# LCmeter0-LCD-mounted-PIC-COMP.net
KiCad netlist of a schematic drawn in EAGLE
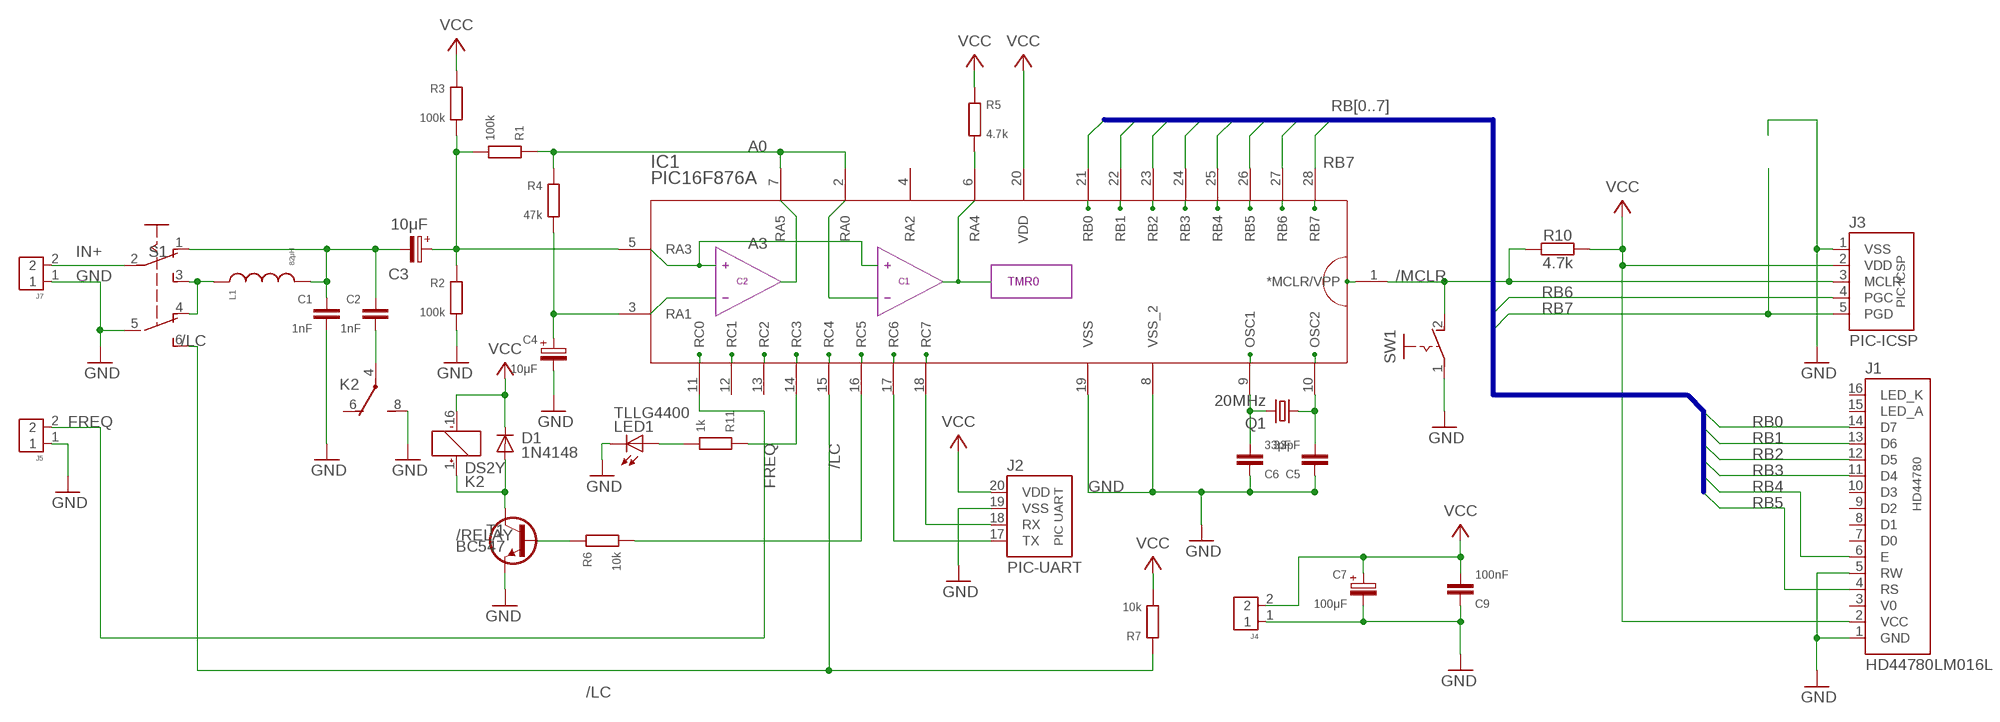
[diagram p0: schematic, sheet 1]

(export (version "E")
  (design (tool "Eeschema 10.0.6"))
  (components
    (comp (ref "C1")
      (value "1nF")
      (footprint "eagle-import:C050-025X060")
      (libsource (lib "eagle-import") (part "C025-025X060"))
    )
    (comp (ref "C2")
      (value "1nF")
      (footprint "eagle-import:C050-025X060")
      (libsource (lib "eagle-import") (part "C025-025X060"))
    )
    (comp (ref "C3")
      (value "10μF")
      (footprint "eagle-import:E2,5-4")
      (libsource (lib "eagle-import") (part "CPOLE2,5-4"))
    )
    (comp (ref "C4")
      (value "10μF")
      (footprint "eagle-import:E2,5-4")
      (libsource (lib "eagle-import") (part "CPOLE2,5-4"))
    )
    (comp (ref "C5")
      (value "33pF")
      (footprint "eagle-import:C025-020X036")
      (libsource (lib "eagle-import") (part "C025-020X036"))
    )
    (comp (ref "C6")
      (value "33pF")
      (footprint "eagle-import:C025-020X036")
      (libsource (lib "eagle-import") (part "C025-020X036"))
    )
    (comp (ref "C7")
      (value "100μF")
      (footprint "eagle-import:E2,5-5")
      (libsource (lib "eagle-import") (part "CPOLE2.5-5"))
    )
    (comp (ref "C9")
      (value "100nF")
      (footprint "eagle-import:C025-020X036_V")
      (libsource (lib "eagle-import") (part "C025-020X036/V"))
    )
    (comp (ref "D1")
      (value "1N4148")
      (footprint "eagle-import:DO34-7")
      (libsource (lib "eagle-import") (part "1N414834-7"))
    )
    (comp (ref "IC1")
      (value "PIC16F876A")
      (footprint "eagle-import:DIL28-3")
      (libsource (lib "eagle-import") (part "PIC16F876A-X/SP-COMP-B-A"))
    )
    (comp (ref "J1")
      (value "HD44780LM016L")
      (footprint "eagle-import:LM016L-HD44780")
      (libsource (lib "eagle-import") (part "HD44780LM016L"))
    )
    (comp (ref "J2")
      (value "PIC-UART")
      (footprint "eagle-import:PIC-UART")
      (libsource (lib "eagle-import") (part "PIC-UART"))
    )
    (comp (ref "J3")
      (value "PIC-ICSP")
      (footprint "eagle-import:PIC-ICSP")
      (libsource (lib "eagle-import") (part "PIC-ICSPICSP"))
    )
    (comp (ref "J4")
      (value "J4")
      (footprint "eagle-import:CONN-2P")
      (libsource (lib "eagle-import") (part "CONN-2P2P/H"))
    )
    (comp (ref "J5")
      (value "CONN-2P2P/V")
      (footprint "eagle-import:CONN-2P-V")
      (libsource (lib "eagle-import") (part "CONN-2P2P/V"))
    )
    (comp (ref "J7")
      (value "CONN-2P2P/V")
      (footprint "eagle-import:CONN-2P-V")
      (libsource (lib "eagle-import") (part "CONN-2P2P/V"))
    )
    (comp (ref "K2")
      (value "DS2Y")
      (footprint "eagle-import:DS2Y")
      (fields (field (name "MPN") "DS2Y-S-DC5V"))
      (libsource (lib "eagle-import") (part "DS2Y-S-DC5V"))
    )
    (comp (ref "L1")
      (value "82μH")
      (footprint "eagle-import:0207_10")
      (libsource (lib "eagle-import") (part "LAXIAL"))
    )
    (comp (ref "LED1")
      (value "TLLG4400")
      (footprint "eagle-import:LED3MM")
      (fields (field (name "MF") "VISHAY SEMICONDUCTOR"))
      (libsource (lib "eagle-import") (part "TLLG4400"))
    )
    (comp (ref "Q1")
      (value "20MHz")
      (footprint "eagle-import:HC49")
      (libsource (lib "eagle-import") (part "CRYSTALHC49"))
    )
    (comp (ref "R1")
      (value "100k")
      (footprint "eagle-import:0202_7")
      (libsource (lib "eagle-import") (part "R0202/7"))
    )
    (comp (ref "R2")
      (value "100k")
      (footprint "eagle-import:0202_7")
      (libsource (lib "eagle-import") (part "R0202/7"))
    )
    (comp (ref "R3")
      (value "100k")
      (footprint "eagle-import:0202_7")
      (libsource (lib "eagle-import") (part "R0202/7"))
    )
    (comp (ref "R4")
      (value "47k")
      (footprint "eagle-import:0202_7")
      (libsource (lib "eagle-import") (part "R0202/7"))
    )
    (comp (ref "R5")
      (value "4.7k")
      (footprint "eagle-import:0202_7")
      (libsource (lib "eagle-import") (part "R0202/7"))
    )
    (comp (ref "R6")
      (value "10k")
      (footprint "eagle-import:0202_10")
      (libsource (lib "eagle-import") (part "R0202/10"))
    )
    (comp (ref "R7")
      (value "10k")
      (footprint "eagle-import:0202_7")
      (libsource (lib "eagle-import") (part "R0202/7"))
    )
    (comp (ref "R10")
      (value "4.7k")
      (footprint "eagle-import:0202_7")
      (libsource (lib "eagle-import") (part "R0202/7"))
    )
    (comp (ref "R11")
      (value "1k")
      (footprint "eagle-import:0202_10-V")
      (libsource (lib "eagle-import") (part "R0202/10-V"))
    )
    (comp (ref "S1")
      (value "SL-SW-2P-2T")
      (footprint "eagle-import:SLSW-2P2T")
      (libsource (lib "eagle-import") (part "SL-SW-2P-2T"))
    )
    (comp (ref "SW1")
      (value "PB-1P-1T")
      (footprint "eagle-import:PB-1P1T")
      (libsource (lib "eagle-import") (part "PB-1P-1T"))
    )
    (comp (ref "T1")
      (value "BC547")
      (footprint "eagle-import:TO92-CBE")
      (libsource (lib "eagle-import") (part "BC547CBE"))
    )
  )
  (nets
    (net (code "1") (name "/A0") (class "Default")
      (node (ref "IC1") (pin "2") (pinfunction "RA0_2") (pintype "passive"))
      (node (ref "IC1") (pin "7") (pinfunction "RA5_7") (pintype "passive"))
      (node (ref "R1") (pin "2") (pinfunction "2_2") (pintype "passive"))
      (node (ref "R4") (pin "2") (pinfunction "2_2") (pintype "passive"))
    )
    (net (code "2") (name "/A3") (class "Default")
      (node (ref "C3") (pin "+") (pinfunction "+_+") (pintype "passive"))
      (node (ref "IC1") (pin "5") (pinfunction "RA3_5") (pintype "passive"))
      (node (ref "R1") (pin "1") (pinfunction "1_1") (pintype "passive"))
      (node (ref "R2") (pin "2") (pinfunction "2_2") (pintype "passive"))
      (node (ref "R3") (pin "1") (pinfunction "1_1") (pintype "passive"))
    )
    (net (code "3") (name "/FREQ") (class "Default")
      (node (ref "IC1") (pin "11") (pinfunction "RC0_11") (pintype "passive"))
      (node (ref "J5") (pin "2") (pinfunction "2_2") (pintype "bidirectional"))
    )
    (net (code "4") (name "/IN+") (class "Default")
      (node (ref "J7") (pin "2") (pinfunction "2_2") (pintype "bidirectional"))
      (node (ref "S1") (pin "2") (pinfunction "P_2") (pintype "passive"))
    )
    (net (code "5") (name "/RB0") (class "Default")
      (node (ref "IC1") (pin "21") (pinfunction "RB0_21") (pintype "passive"))
      (node (ref "J1") (pin "14") (pinfunction "D7_14") (pintype "passive"))
    )
    (net (code "6") (name "/RB1") (class "Default")
      (node (ref "IC1") (pin "22") (pinfunction "RB1_22") (pintype "passive"))
      (node (ref "J1") (pin "13") (pinfunction "D6_13") (pintype "passive"))
    )
    (net (code "7") (name "/RB2") (class "Default")
      (node (ref "IC1") (pin "23") (pinfunction "RB2_23") (pintype "passive"))
      (node (ref "J1") (pin "12") (pinfunction "D5_12") (pintype "passive"))
    )
    (net (code "8") (name "/RB3") (class "Default")
      (node (ref "IC1") (pin "24") (pinfunction "RB3_24") (pintype "passive"))
      (node (ref "J1") (pin "11") (pinfunction "D4_11") (pintype "passive"))
    )
    (net (code "9") (name "/RB4") (class "Default")
      (node (ref "IC1") (pin "25") (pinfunction "RB4_25") (pintype "passive"))
      (node (ref "J1") (pin "6") (pinfunction "E_6") (pintype "passive"))
    )
    (net (code "10") (name "/RB5") (class "Default")
      (node (ref "IC1") (pin "26") (pinfunction "RB5_26") (pintype "passive"))
      (node (ref "J1") (pin "4") (pinfunction "RS_4") (pintype "passive"))
    )
    (net (code "11") (name "/RB6") (class "Default")
      (node (ref "IC1") (pin "27") (pinfunction "RB6_27") (pintype "passive"))
      (node (ref "J3") (pin "4") (pinfunction "PGC_4") (pintype "passive"))
    )
    (net (code "12") (name "/RB7") (class "Default")
      (node (ref "IC1") (pin "28") (pinfunction "RB7_28") (pintype "passive"))
      (node (ref "J3") (pin "5") (pinfunction "PGD_5") (pintype "passive"))
    )
    (net (code "14") (name "/{slash}LC") (class "Default")
      (node (ref "IC1") (pin "15") (pinfunction "RC4_15") (pintype "passive"))
      (node (ref "R7") (pin "2") (pinfunction "2_2") (pintype "passive"))
      (node (ref "S1") (pin "6") (pinfunction "S1_6") (pintype "passive"))
    )
    (net (code "15") (name "/{slash}MCLR") (class "Default")
      (node (ref "IC1") (pin "1") (pinfunction "*MCLR/VPP_1") (pintype "passive"))
      (node (ref "J3") (pin "3") (pinfunction "MCLR_3") (pintype "passive"))
      (node (ref "R10") (pin "2") (pinfunction "2_2") (pintype "passive"))
      (node (ref "SW1") (pin "2") (pinfunction "S_2") (pintype "passive"))
    )
    (net (code "16") (name "/{slash}RELAY") (class "Default")
      (node (ref "D1") (pin "A") (pinfunction "A_A") (pintype "passive"))
      (node (ref "K2") (pin "1") (pinfunction "+_1") (pintype "passive"))
      (node (ref "T1") (pin "C") (pinfunction "C_C") (pintype "passive"))
    )
    (net (code "17") (name "GND") (class "Default")
      (node (ref "C1") (pin "2") (pinfunction "2_2") (pintype "passive"))
      (node (ref "C4") (pin "-") (pinfunction "-_-") (pintype "passive"))
      (node (ref "C5") (pin "1") (pinfunction "1_1") (pintype "passive"))
      (node (ref "C6") (pin "1") (pinfunction "1_1") (pintype "passive"))
      (node (ref "C7") (pin "-") (pinfunction "-_-") (pintype "passive"))
      (node (ref "C9") (pin "1") (pinfunction "1_1") (pintype "passive"))
      (node (ref "IC1") (pin "19") (pinfunction "VSS_19") (pintype "passive"))
      (node (ref "IC1") (pin "8") (pinfunction "VSS_2_8") (pintype "passive"))
      (node (ref "J1") (pin "1") (pinfunction "GND_1") (pintype "passive"))
      (node (ref "J1") (pin "5") (pinfunction "RW_5") (pintype "passive"))
      (node (ref "J2") (pin "19") (pinfunction "VSS_19") (pintype "passive"))
      (node (ref "J3") (pin "1") (pinfunction "VSS_1") (pintype "passive"))
      (node (ref "J4") (pin "1") (pinfunction "1_1") (pintype "bidirectional"))
      (node (ref "J5") (pin "1") (pinfunction "1_1") (pintype "bidirectional"))
      (node (ref "J7") (pin "1") (pinfunction "1_1") (pintype "bidirectional"))
      (node (ref "K2") (pin "8") (pinfunction "S_8") (pintype "passive"))
      (node (ref "LED1") (pin "K") (pinfunction "C_K") (pintype "passive"))
      (node (ref "R2") (pin "1") (pinfunction "1_1") (pintype "passive"))
      (node (ref "S1") (pin "5") (pinfunction "P1_5") (pintype "passive"))
      (node (ref "SW1") (pin "1") (pinfunction "P_1") (pintype "passive"))
      (node (ref "T1") (pin "E") (pinfunction "E_E") (pintype "passive"))
    )
    (net (code "18") (name "Net-(IC1-OSC1)") (class "Default")
      (node (ref "C6") (pin "2") (pinfunction "2_2") (pintype "passive"))
      (node (ref "IC1") (pin "9") (pinfunction "OSC1_9") (pintype "passive"))
      (node (ref "Q1") (pin "2") (pinfunction "2_2") (pintype "passive"))
    )
    (net (code "19") (name "Net-(IC1-OSC2)") (class "Default")
      (node (ref "C5") (pin "2") (pinfunction "2_2") (pintype "passive"))
      (node (ref "IC1") (pin "10") (pinfunction "OSC2_10") (pintype "passive"))
      (node (ref "Q1") (pin "1") (pinfunction "1_1") (pintype "passive"))
    )
    (net (code "20") (name "Net-(IC1-RA1)") (class "Default")
      (node (ref "C4") (pin "+") (pinfunction "+_+") (pintype "passive"))
      (node (ref "IC1") (pin "3") (pinfunction "RA1_3") (pintype "passive"))
      (node (ref "R4") (pin "1") (pinfunction "1_1") (pintype "passive"))
    )
    (net (code "21") (name "Net-(IC1-RA4)") (class "Default")
      (node (ref "IC1") (pin "6") (pinfunction "RA4_6") (pintype "passive"))
      (node (ref "R5") (pin "1") (pinfunction "1_1") (pintype "passive"))
    )
    (net (code "22") (name "Net-(IC1-RC3)") (class "Default")
      (node (ref "IC1") (pin "14") (pinfunction "RC3_14") (pintype "passive"))
      (node (ref "R11") (pin "2") (pinfunction "2_2") (pintype "passive"))
    )
    (net (code "23") (name "Net-(IC1-RC5)") (class "Default")
      (node (ref "IC1") (pin "16") (pinfunction "RC5_16") (pintype "passive"))
      (node (ref "R6") (pin "1") (pinfunction "1_1") (pintype "passive"))
    )
    (net (code "24") (name "Net-(IC1-RC6)") (class "Default")
      (node (ref "IC1") (pin "17") (pinfunction "RC6_17") (pintype "passive"))
      (node (ref "J2") (pin "17") (pinfunction "TX_17") (pintype "passive"))
    )
    (net (code "25") (name "Net-(IC1-RC7)") (class "Default")
      (node (ref "IC1") (pin "18") (pinfunction "RC7_18") (pintype "passive"))
      (node (ref "J2") (pin "18") (pinfunction "RX_18") (pintype "passive"))
    )
    (net (code "26") (name "Net-(K2B-P)") (class "Default")
      (node (ref "C2") (pin "2") (pinfunction "2_2") (pintype "passive"))
      (node (ref "K2") (pin "4") (pinfunction "P_4") (pintype "passive"))
    )
    (net (code "27") (name "Net-(LED1-PadA)") (class "Default")
      (node (ref "LED1") (pin "A") (pinfunction "A_A") (pintype "passive"))
      (node (ref "R11") (pin "1") (pinfunction "1_1") (pintype "passive"))
    )
    (net (code "28") (name "Net-(R6-Pad2)") (class "Default")
      (node (ref "R6") (pin "2") (pinfunction "2_2") (pintype "passive"))
      (node (ref "T1") (pin "B") (pinfunction "B_B") (pintype "passive"))
    )
    (net (code "29") (name "Net-(S1-O)") (class "Default")
      (node (ref "C1") (pin "1") (pinfunction "1_1") (pintype "passive"))
      (node (ref "C2") (pin "1") (pinfunction "1_1") (pintype "passive"))
      (node (ref "C3") (pin "-") (pinfunction "-_-") (pintype "passive"))
      (node (ref "L1") (pin "2") (pinfunction "2_2") (pintype "passive"))
      (node (ref "S1") (pin "1") (pinfunction "O_1") (pintype "passive"))
    )
    (net (code "30") (name "Net-(S1-O1)") (class "Default")
      (node (ref "L1") (pin "1") (pinfunction "1_1") (pintype "passive"))
      (node (ref "S1") (pin "3") (pinfunction "S_3") (pintype "passive"))
      (node (ref "S1") (pin "4") (pinfunction "O1_4") (pintype "passive"))
    )
    (net (code "31") (name "VCC") (class "Default")
      (node (ref "C7") (pin "+") (pinfunction "+_+") (pintype "passive"))
      (node (ref "C9") (pin "2") (pinfunction "2_2") (pintype "passive"))
      (node (ref "D1") (pin "C") (pinfunction "C_C") (pintype "passive"))
      (node (ref "IC1") (pin "20") (pinfunction "VDD_20") (pintype "passive"))
      (node (ref "J1") (pin "2") (pinfunction "VCC_2") (pintype "passive"))
      (node (ref "J2") (pin "20") (pinfunction "VDD_20") (pintype "passive"))
      (node (ref "J3") (pin "2") (pinfunction "VDD_2") (pintype "passive"))
      (node (ref "J4") (pin "2") (pinfunction "2_2") (pintype "bidirectional"))
      (node (ref "K2") (pin "16") (pinfunction "-_16") (pintype "passive"))
      (node (ref "R10") (pin "1") (pinfunction "1_1") (pintype "passive"))
      (node (ref "R3") (pin "2") (pinfunction "2_2") (pintype "passive"))
      (node (ref "R5") (pin "2") (pinfunction "2_2") (pintype "passive"))
      (node (ref "R7") (pin "1") (pinfunction "1_1") (pintype "passive"))
    )
    (net (code "32") (name "unconnected-(IC1-RA2-Pad4)") (class "Default")
      (node (ref "IC1") (pin "4") (pinfunction "RA2_4") (pintype "passive"))
    )
    (net (code "33") (name "unconnected-(IC1-RC1-Pad12)") (class "Default")
      (node (ref "IC1") (pin "12") (pinfunction "RC1_12") (pintype "passive"))
    )
    (net (code "34") (name "unconnected-(IC1-RC2-Pad13)") (class "Default")
      (node (ref "IC1") (pin "13") (pinfunction "RC2_13") (pintype "passive"))
    )
    (net (code "35") (name "unconnected-(J1-D0-Pad7)") (class "Default")
      (node (ref "J1") (pin "7") (pinfunction "D0_7") (pintype "passive"))
    )
    (net (code "36") (name "unconnected-(J1-D1-Pad8)") (class "Default")
      (node (ref "J1") (pin "8") (pinfunction "D1_8") (pintype "passive"))
    )
    (net (code "37") (name "unconnected-(J1-D2-Pad9)") (class "Default")
      (node (ref "J1") (pin "9") (pinfunction "D2_9") (pintype "passive"))
    )
    (net (code "38") (name "unconnected-(J1-D3-Pad10)") (class "Default")
      (node (ref "J1") (pin "10") (pinfunction "D3_10") (pintype "passive"))
    )
    (net (code "39") (name "unconnected-(J1-LED_A-Pad15)") (class "Default")
      (node (ref "J1") (pin "15") (pinfunction "LED_A_15") (pintype "passive"))
    )
    (net (code "40") (name "unconnected-(J1-LED_K-Pad16)") (class "Default")
      (node (ref "J1") (pin "16") (pinfunction "LED_K_16") (pintype "passive"))
    )
    (net (code "41") (name "unconnected-(J1-V0-Pad3)") (class "Default")
      (node (ref "J1") (pin "3") (pinfunction "V0_3") (pintype "passive"))
    )
    (net (code "42") (name "unconnected-(K2B-O-Pad6)") (class "Default")
      (node (ref "K2") (pin "6") (pinfunction "O_6") (pintype "passive"))
    )
  )
)
